# switch.net
KiCad netlist of a schematic drawn in Altium Designer
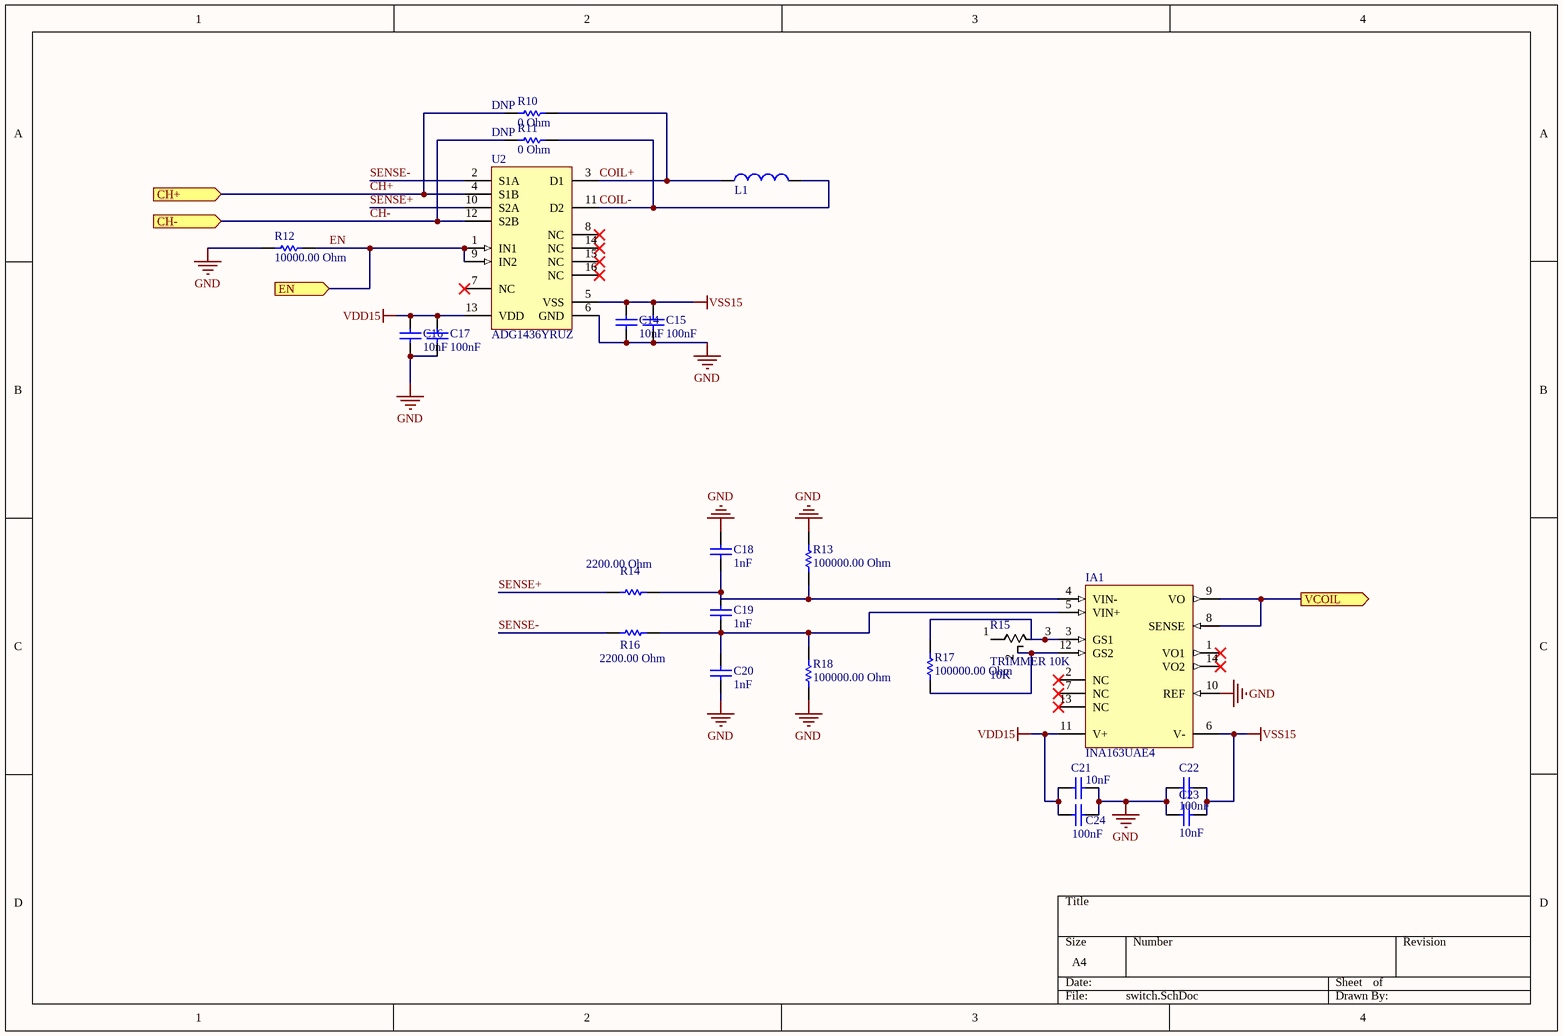
[diagram p0: switch.SchDoc]

(export (version "E")
  (design (tool "Eeschema 10.0.6"))
  (components
    (comp (ref "C14")
      (value "10nF")
      (footprint "CAPC0603(1608)100_N")
      (description "CAP 10nF 25V ±10% 0603 (1608 Metric) Thickness 1mm SMD")
      (fields (field (name "TOLERANCE") "Â±10%") (field (name "Comment") "CAP 10nF 25V 0603(1608)"))
      (libsource (lib "Altium Content Vault") (part "CMP-1035-02317-1"))
    )
    (comp (ref "C15")
      (value "100nF")
      (footprint "CAPC0603(1608)100_M")
      (description "CAP 100nF 25V ±10% 0603 (1608 Metric) Thickness 1mm SMD")
      (fields (field (name "TOLERANCE") "Â±10%") (field (name "Comment") "CAP 100nF 25V 0603(1608)"))
      (libsource (lib "Altium Content Vault") (part "CMP-1035-02588-1"))
    )
    (comp (ref "C16")
      (value "10nF")
      (footprint "CAPC0603(1608)100_N")
      (description "CAP 10nF 25V ±10% 0603 (1608 Metric) Thickness 1mm SMD")
      (fields (field (name "TOLERANCE") "Â±10%") (field (name "Comment") "CAP 10nF 25V 0603(1608)"))
      (libsource (lib "Altium Content Vault") (part "CMP-1035-02317-1"))
    )
    (comp (ref "C17")
      (value "100nF")
      (footprint "CAPC0603(1608)100_M")
      (description "CAP 100nF 25V ±10% 0603 (1608 Metric) Thickness 1mm SMD")
      (fields (field (name "TOLERANCE") "Â±10%") (field (name "Comment") "CAP 100nF 25V 0603(1608)"))
      (libsource (lib "Altium Content Vault") (part "CMP-1035-02588-1"))
    )
    (comp (ref "C18")
      (value "1nF")
      (footprint "CAPC0603(1608)100_M")
      (description "CAP 1nF 25V ±5% 0603 (1608 Metric) Thickness 1mm SMD")
      (fields (field (name "TOLERANCE") "Â±5%") (field (name "Comment") "CAP 1nF 25V 0603(1608)"))
      (libsource (lib "Altium Content Vault") (part "CMP-1035-01883-1"))
    )
    (comp (ref "C19")
      (value "1nF")
      (footprint "CAPC0603(1608)100_M")
      (description "CAP 1nF 25V ±5% 0603 (1608 Metric) Thickness 1mm SMD")
      (fields (field (name "TOLERANCE") "Â±5%") (field (name "Comment") "CAP 1nF 25V 0603(1608)"))
      (libsource (lib "Altium Content Vault") (part "CMP-1035-01883-1"))
    )
    (comp (ref "C20")
      (value "1nF")
      (footprint "CAPC0603(1608)100_M")
      (description "CAP 1nF 25V ±5% 0603 (1608 Metric) Thickness 1mm SMD")
      (fields (field (name "TOLERANCE") "Â±5%") (field (name "Comment") "CAP 1nF 25V 0603(1608)"))
      (libsource (lib "Altium Content Vault") (part "CMP-1035-01883-1"))
    )
    (comp (ref "C21")
      (value "10nF")
      (footprint "CAPC0603(1608)100_N")
      (description "CAP 10nF 25V ±10% 0603 (1608 Metric) Thickness 1mm SMD")
      (fields (field (name "TOLERANCE") "Â±10%") (field (name "Comment") "CAP 10nF 25V 0603(1608)"))
      (libsource (lib "Altium Content Vault") (part "CMP-1035-02317-1"))
    )
    (comp (ref "C22")
      (value "100nF")
      (footprint "CAPC0603(1608)100_M")
      (description "CAP 100nF 25V ±10% 0603 (1608 Metric) Thickness 1mm SMD")
      (fields (field (name "TOLERANCE") "Â±10%") (field (name "Comment") "CAP 100nF 25V 0603(1608)"))
      (libsource (lib "Altium Content Vault") (part "CMP-1035-02588-1"))
    )
    (comp (ref "C23")
      (value "10nF")
      (footprint "CAPC0603(1608)100_N")
      (description "CAP 10nF 25V ±10% 0603 (1608 Metric) Thickness 1mm SMD")
      (fields (field (name "TOLERANCE") "Â±10%") (field (name "Comment") "CAP 10nF 25V 0603(1608)"))
      (libsource (lib "Altium Content Vault") (part "CMP-1035-02317-1"))
    )
    (comp (ref "C24")
      (value "100nF")
      (footprint "CAPC0603(1608)100_M")
      (description "CAP 100nF 25V ±10% 0603 (1608 Metric) Thickness 1mm SMD")
      (fields (field (name "TOLERANCE") "Â±10%") (field (name "Comment") "CAP 100nF 25V 0603(1608)"))
      (libsource (lib "Altium Content Vault") (part "CMP-1035-02588-1"))
    )
    (comp (ref "IA1")
      (value "INA163UAE4")
      (footprint "TI-D14_M")
      (fields (field (name "MANUFACTURER") "Texas Instruments"))
      (libsource (lib "Altium Content Vault") (part "CMP-0944-00014-1"))
    )
    (comp (ref "L1")
      (value "~")
      (footprint "TRANSMITTER_COIL_UCC_ORIGINAL")
      (description "TRANSMITTER_COIL_UCC_ORIGINAL")
      (libsource (lib "Transmitter_PCB") (part "TRANSMITTER_COIL_UCC_ORIGINAL"))
    )
    (comp (ref "R10")
      (value "0 Ohm")
      (footprint "RESC0603(1608)_L")
      (description "1K 0.1W 5% 0603 (1608 Metric)  SMD")
      (fields (field (name "TOLERANCE") "5 %") (field (name "POWER") "0.1 W") (field (name "DNP") "DNP"))
      (libsource (lib "Altium Content Vault") (part "CMP-1012-00074-1"))
    )
    (comp (ref "R11")
      (value "0 Ohm")
      (footprint "RESC0603(1608)_L")
      (description "1K 0.1W 5% 0603 (1608 Metric)  SMD")
      (fields (field (name "TOLERANCE") "5 %") (field (name "POWER") "0.1 W") (field (name "DNP") "DNP"))
      (libsource (lib "Altium Content Vault") (part "CMP-1012-00074-1"))
    )
    (comp (ref "R12")
      (value "10000.00 Ohm")
      (footprint "RESC0603(1608)_L")
      (description "1K 0.1W 5% 0603 (1608 Metric)  SMD")
      (fields (field (name "TOLERANCE") "5 %") (field (name "POWER") "0.1 W"))
      (libsource (lib "Altium Content Vault") (part "CMP-1012-00074-1"))
    )
    (comp (ref "R13")
      (value "100000.00 Ohm")
      (footprint "RESC0603(1608)_N")
      (description "100K 0.1W 5% 0603 (1608 Metric)  SMD")
      (fields (field (name "TOLERANCE") "5 %") (field (name "POWER") "0.1 W"))
      (libsource (lib "Altium Content Vault") (part "CMP-1012-00122-1"))
    )
    (comp (ref "R14")
      (value "2200.00 Ohm")
      (footprint "RESC0603(1608)_L")
      (description "2K2 0.1W 1% 0603 (1608 Metric)  SMD")
      (fields (field (name "TOLERANCE") "1 %") (field (name "POWER") "0.1 W"))
      (libsource (lib "Altium Content Vault") (part "CMP-1012-00546-1"))
    )
    (comp (ref "R15")
      (value "TRIMMER 10K")
      (footprint "TRIMMER 10K")
      (description "TRIMMER 10K OHM 0.5W TH")
      (fields
        (field (name "MANUFACTURER") "TE Connectivity Passive Product")
        (field (name "MANUFACTURER PART NUMBER") "1-1623849-0")
        (field (name "ALTIUM_VALUE") "10K")
        (field (name "PUBLISHER") "Altium Limited")
      )
      (libsource (lib "AnserEMT") (part "TRIMMER 10K"))
    )
    (comp (ref "R16")
      (value "2200.00 Ohm")
      (footprint "RESC0603(1608)_L")
      (description "2K2 0.1W 1% 0603 (1608 Metric)  SMD")
      (fields (field (name "TOLERANCE") "1 %") (field (name "POWER") "0.1 W"))
      (libsource (lib "Altium Content Vault") (part "CMP-1012-00546-1"))
    )
    (comp (ref "R17")
      (value "100000.00 Ohm")
      (footprint "RESC0603(1608)_N")
      (description "100K 0.1W 5% 0603 (1608 Metric)  SMD")
      (fields (field (name "TOLERANCE") "5 %") (field (name "POWER") "0.1 W"))
      (libsource (lib "Altium Content Vault") (part "CMP-1012-00122-1"))
    )
    (comp (ref "R18")
      (value "100000.00 Ohm")
      (footprint "RESC0603(1608)_N")
      (description "100K 0.1W 5% 0603 (1608 Metric)  SMD")
      (fields (field (name "TOLERANCE") "5 %") (field (name "POWER") "0.1 W"))
      (libsource (lib "Altium Content Vault") (part "CMP-1012-00122-1"))
    )
    (comp (ref "U2")
      (value "ADG1436YRUZ")
      (footprint "ADI-RU-16_L")
      (description "+/-15 V / 12 V / +/-5 V, iCMOS, Dual SPDT Switch, 16-pin SOP (RU-16), Tube")
      (fields (field (name "MANUFACTURER") "Analog Devices"))
      (libsource (lib "Altium Content Vault") (part "CMP-0793-00124-1"))
    )
  )
  (nets
    (net (code "1") (name "/CH+") (class "Default")
      (node (ref "R10") (pin "1") (pinfunction "1_1") (pintype "passive"))
      (node (ref "U2") (pin "4") (pinfunction "S1B_4") (pintype "passive"))
    )
    (net (code "2") (name "/CH-") (class "Default")
      (node (ref "R11") (pin "1") (pinfunction "1_1") (pintype "passive"))
      (node (ref "U2") (pin "12") (pinfunction "S2B_12") (pintype "passive"))
    )
    (net (code "3") (name "/COIL+") (class "Default")
      (node (ref "L1") (pin "2") (pinfunction "2_2") (pintype "passive"))
      (node (ref "R10") (pin "2") (pinfunction "2_2") (pintype "passive"))
      (node (ref "U2") (pin "3") (pinfunction "D1_3") (pintype "passive"))
    )
    (net (code "4") (name "/COIL-") (class "Default")
      (node (ref "L1") (pin "1") (pinfunction "1_1") (pintype "passive"))
      (node (ref "R11") (pin "2") (pinfunction "2_2") (pintype "passive"))
      (node (ref "U2") (pin "11") (pinfunction "D2_11") (pintype "passive"))
    )
    (net (code "5") (name "/EN") (class "Default")
      (node (ref "R12") (pin "2") (pinfunction "2_2") (pintype "passive"))
      (node (ref "U2") (pin "1") (pinfunction "IN1_1") (pintype "input"))
      (node (ref "U2") (pin "9") (pinfunction "IN2_9") (pintype "input"))
    )
    (net (code "6") (name "/SENSE+") (class "Default")
      (node (ref "R14") (pin "2") (pinfunction "2_2") (pintype "passive"))
      (node (ref "U2") (pin "10") (pinfunction "S2A_10") (pintype "passive"))
    )
    (net (code "7") (name "/SENSE-") (class "Default")
      (node (ref "R16") (pin "2") (pinfunction "2_2") (pintype "passive"))
      (node (ref "U2") (pin "2") (pinfunction "S1A_2") (pintype "passive"))
    )
    (net (code "8") (name "/VCOIL") (class "Default")
      (node (ref "IA1") (pin "8") (pinfunction "SENSE_8") (pintype "input"))
      (node (ref "IA1") (pin "9") (pinfunction "VO_9") (pintype "output"))
    )
    (net (code "9") (name "GND") (class "Default")
      (node (ref "C14") (pin "1") (pinfunction "1_1") (pintype "passive"))
      (node (ref "C15") (pin "2") (pinfunction "2_2") (pintype "passive"))
      (node (ref "C16") (pin "1") (pinfunction "1_1") (pintype "passive"))
      (node (ref "C17") (pin "2") (pinfunction "2_2") (pintype "passive"))
      (node (ref "C18") (pin "2") (pinfunction "2_2") (pintype "passive"))
      (node (ref "C20") (pin "1") (pinfunction "1_1") (pintype "passive"))
      (node (ref "C21") (pin "2") (pinfunction "2_2") (pintype "passive"))
      (node (ref "C22") (pin "1") (pinfunction "1_1") (pintype "passive"))
      (node (ref "C23") (pin "2") (pinfunction "2_2") (pintype "passive"))
      (node (ref "C24") (pin "1") (pinfunction "1_1") (pintype "passive"))
      (node (ref "IA1") (pin "10") (pinfunction "REF_10") (pintype "input"))
      (node (ref "R12") (pin "1") (pinfunction "1_1") (pintype "passive"))
      (node (ref "R13") (pin "1") (pinfunction "1_1") (pintype "passive"))
      (node (ref "R18") (pin "2") (pinfunction "2_2") (pintype "passive"))
      (node (ref "U2") (pin "6") (pinfunction "GND_6") (pintype "power_in"))
    )
    (net (code "10") (name "Net-(IA1-GS1)") (class "Default")
      (node (ref "IA1") (pin "3") (pinfunction "GS1_3") (pintype "input"))
      (node (ref "R15") (pin "3") (pinfunction "3_3") (pintype "passive"))
      (node (ref "R17") (pin "1") (pinfunction "1_1") (pintype "passive"))
    )
    (net (code "11") (name "Net-(IA1-GS2)") (class "Default")
      (node (ref "IA1") (pin "12") (pinfunction "GS2_12") (pintype "input"))
      (node (ref "R15") (pin "2") (pinfunction "2_2") (pintype "passive"))
      (node (ref "R17") (pin "2") (pinfunction "2_2") (pintype "passive"))
    )
    (net (code "12") (name "Net-(IA1-VIN+)") (class "Default")
      (node (ref "C19") (pin "1") (pinfunction "1_1") (pintype "passive"))
      (node (ref "C20") (pin "2") (pinfunction "2_2") (pintype "passive"))
      (node (ref "IA1") (pin "5") (pinfunction "VIN+_5") (pintype "input"))
      (node (ref "R16") (pin "1") (pinfunction "1_1") (pintype "passive"))
      (node (ref "R18") (pin "1") (pinfunction "1_1") (pintype "passive"))
    )
    (net (code "13") (name "Net-(IA1-VIN-)") (class "Default")
      (node (ref "C18") (pin "1") (pinfunction "1_1") (pintype "passive"))
      (node (ref "C19") (pin "2") (pinfunction "2_2") (pintype "passive"))
      (node (ref "IA1") (pin "4") (pinfunction "VIN-_4") (pintype "input"))
      (node (ref "R13") (pin "2") (pinfunction "2_2") (pintype "passive"))
      (node (ref "R14") (pin "1") (pinfunction "1_1") (pintype "passive"))
    )
    (net (code "14") (name "VDD15") (class "Default")
      (node (ref "C16") (pin "2") (pinfunction "2_2") (pintype "passive"))
      (node (ref "C17") (pin "1") (pinfunction "1_1") (pintype "passive"))
      (node (ref "C21") (pin "1") (pinfunction "1_1") (pintype "passive"))
      (node (ref "C24") (pin "2") (pinfunction "2_2") (pintype "passive"))
      (node (ref "IA1") (pin "11") (pinfunction "V+_11") (pintype "power_in"))
      (node (ref "U2") (pin "13") (pinfunction "VDD_13") (pintype "power_in"))
    )
    (net (code "15") (name "VSS15") (class "Default")
      (node (ref "C14") (pin "2") (pinfunction "2_2") (pintype "passive"))
      (node (ref "C15") (pin "1") (pinfunction "1_1") (pintype "passive"))
      (node (ref "C22") (pin "2") (pinfunction "2_2") (pintype "passive"))
      (node (ref "C23") (pin "1") (pinfunction "1_1") (pintype "passive"))
      (node (ref "IA1") (pin "6") (pinfunction "V-_6") (pintype "power_in"))
      (node (ref "U2") (pin "5") (pinfunction "VSS_5") (pintype "power_in"))
    )
    (net (code "16") (name "unconnected-(IA1-NC-Pad2)") (class "Default")
      (node (ref "IA1") (pin "2") (pinfunction "NC_2") (pintype "passive+no_connect"))
    )
    (net (code "17") (name "unconnected-(IA1-NC-Pad7)") (class "Default")
      (node (ref "IA1") (pin "7") (pinfunction "NC_7") (pintype "passive+no_connect"))
    )
    (net (code "18") (name "unconnected-(IA1-NC-Pad13)") (class "Default")
      (node (ref "IA1") (pin "13") (pinfunction "NC_13") (pintype "passive+no_connect"))
    )
    (net (code "19") (name "unconnected-(IA1-VO1-Pad1)") (class "Default")
      (node (ref "IA1") (pin "1") (pinfunction "VO1_1") (pintype "output+no_connect"))
    )
    (net (code "20") (name "unconnected-(IA1-VO2-Pad14)") (class "Default")
      (node (ref "IA1") (pin "14") (pinfunction "VO2_14") (pintype "output+no_connect"))
    )
    (net (code "21") (name "unconnected-(R15-Pad1)") (class "Default")
      (node (ref "R15") (pin "1") (pinfunction "1_1") (pintype "passive"))
    )
    (net (code "22") (name "unconnected-(U2-NC-Pad7)") (class "Default")
      (node (ref "U2") (pin "7") (pinfunction "NC_7") (pintype "passive+no_connect"))
    )
    (net (code "23") (name "unconnected-(U2-NC-Pad8)") (class "Default")
      (node (ref "U2") (pin "8") (pinfunction "NC_8") (pintype "passive+no_connect"))
    )
    (net (code "24") (name "unconnected-(U2-NC-Pad14)") (class "Default")
      (node (ref "U2") (pin "14") (pinfunction "NC_14") (pintype "passive+no_connect"))
    )
    (net (code "25") (name "unconnected-(U2-NC-Pad15)") (class "Default")
      (node (ref "U2") (pin "15") (pinfunction "NC_15") (pintype "passive+no_connect"))
    )
    (net (code "26") (name "unconnected-(U2-NC-Pad16)") (class "Default")
      (node (ref "U2") (pin "16") (pinfunction "NC_16") (pintype "passive+no_connect"))
    )
  )
)
